# uc_board.net
KiCad netlist of a schematic drawn in EAGLE
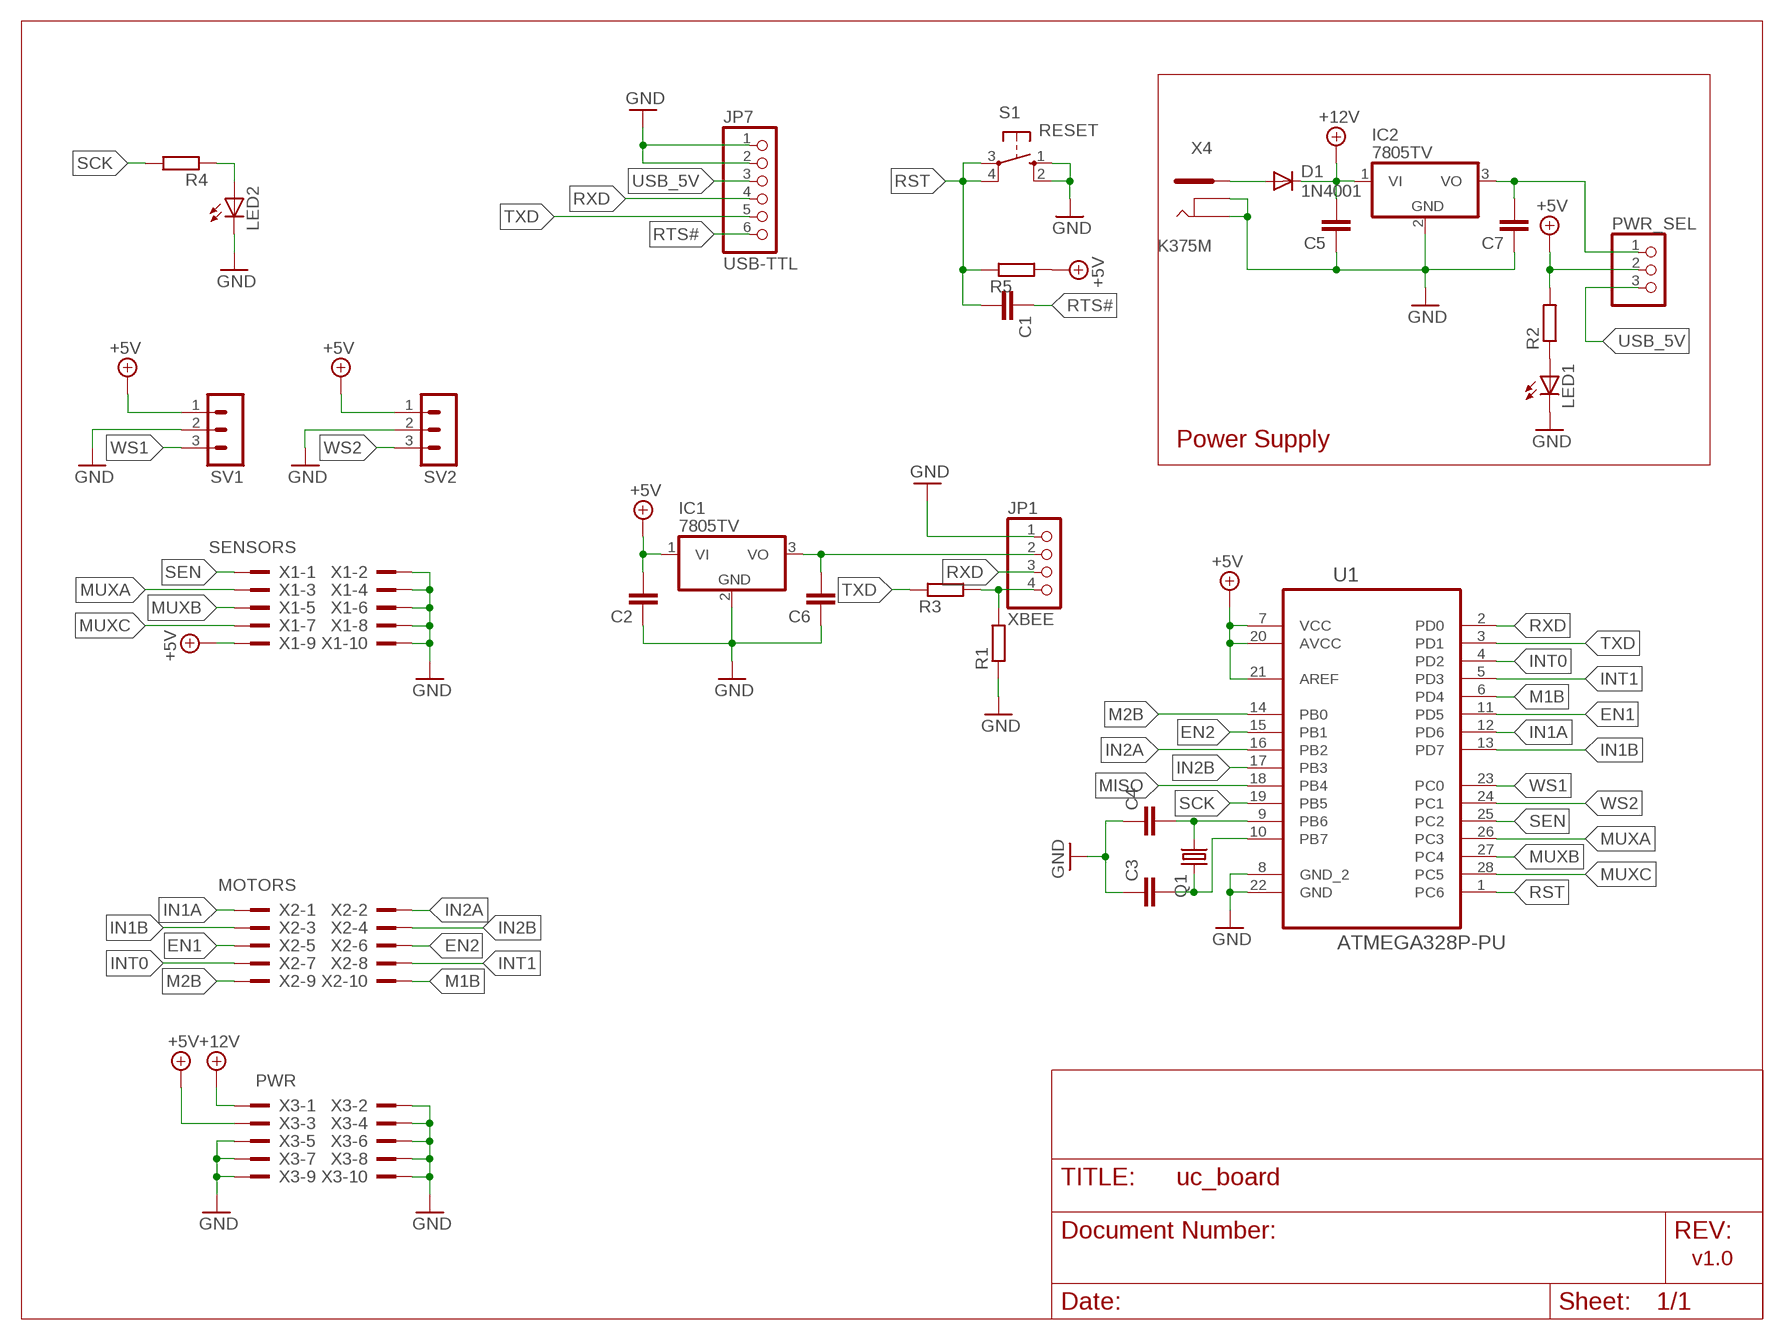
[diagram p0: schematic, sheet 1]

(export (version "E")
  (design (tool "Eeschema 10.0.6"))
  (components
    (comp (ref "C1")
      (value "C-EU050-025X075")
      (footprint "eagle-import:C050-025X075")
      (libsource (lib "eagle-import") (part "C-EU050-025X075"))
    )
    (comp (ref "C2")
      (value "C-EU025-050X050")
      (footprint "eagle-import:C025-050X050")
      (libsource (lib "eagle-import") (part "C-EU025-050X050"))
    )
    (comp (ref "C3")
      (value "C-EU050-024X044")
      (footprint "eagle-import:C050-024X044")
      (libsource (lib "eagle-import") (part "C-EU050-024X044"))
    )
    (comp (ref "C4")
      (value "C-EU050-024X044")
      (footprint "eagle-import:C050-024X044")
      (libsource (lib "eagle-import") (part "C-EU050-024X044"))
    )
    (comp (ref "C5")
      (value "C-EU025-050X050")
      (footprint "eagle-import:C025-050X050")
      (libsource (lib "eagle-import") (part "C-EU025-050X050"))
    )
    (comp (ref "C6")
      (value "C-EU025-050X050")
      (footprint "eagle-import:C025-050X050")
      (libsource (lib "eagle-import") (part "C-EU025-050X050"))
    )
    (comp (ref "C7")
      (value "C-EU025-050X050")
      (footprint "eagle-import:C025-050X050")
      (libsource (lib "eagle-import") (part "C-EU025-050X050"))
    )
    (comp (ref "D1")
      (value "1N4001")
      (footprint "eagle-import:DO41-10")
      (libsource (lib "eagle-import") (part "1N4004"))
    )
    (comp (ref "IC1")
      (value "7805TV")
      (footprint "eagle-import:TO220V")
      (libsource (lib "eagle-import") (part "78TV05"))
    )
    (comp (ref "IC2")
      (value "7805TV")
      (footprint "eagle-import:TO220V")
      (libsource (lib "eagle-import") (part "78TV05"))
    )
    (comp (ref "JP1")
      (value "XBEE")
      (footprint "eagle-import:1X04_90")
      (libsource (lib "eagle-import") (part "PINHD-1X4/90"))
    )
    (comp (ref "JP7")
      (value "USB-TTL")
      (footprint "eagle-import:1X06_90")
      (libsource (lib "eagle-import") (part "PINHD-1X6/90"))
    )
    (comp (ref "LED1")
      (value "LED5MM")
      (footprint "eagle-import:LED5MM")
      (libsource (lib "eagle-import") (part "LED5MM"))
    )
    (comp (ref "LED2")
      (value "LED5MM")
      (footprint "eagle-import:LED5MM")
      (libsource (lib "eagle-import") (part "LED5MM"))
    )
    (comp (ref "PWR_SEL")
      (value "PINHD-1X3")
      (footprint "eagle-import:1X03")
      (libsource (lib "eagle-import") (part "PINHD-1X3"))
    )
    (comp (ref "Q1")
      (value "CRYSTALHC49S")
      (footprint "eagle-import:HC49_S")
      (libsource (lib "eagle-import") (part "CRYSTALHC49S"))
    )
    (comp (ref "R1")
      (value "R-EU_0207/10")
      (footprint "eagle-import:0207_10")
      (libsource (lib "eagle-import") (part "R-EU_0207/10"))
    )
    (comp (ref "R2")
      (value "R-EU_0207/10")
      (footprint "eagle-import:0207_10")
      (libsource (lib "eagle-import") (part "R-EU_0207/10"))
    )
    (comp (ref "R3")
      (value "R-EU_0207/10")
      (footprint "eagle-import:0207_10")
      (libsource (lib "eagle-import") (part "R-EU_0207/10"))
    )
    (comp (ref "R4")
      (value "R-EU_0207/10")
      (footprint "eagle-import:0207_10")
      (libsource (lib "eagle-import") (part "R-EU_0207/10"))
    )
    (comp (ref "R5")
      (value "R-EU_0207/10")
      (footprint "eagle-import:0207_10")
      (libsource (lib "eagle-import") (part "R-EU_0207/10"))
    )
    (comp (ref "S1")
      (value "RESET")
      (footprint "eagle-import:B3F-10XX")
      (fields (field (name "MPN") "B3F-1000"))
      (libsource (lib "eagle-import") (part "10-XX"))
    )
    (comp (ref "SV1")
      (value "MA03-1")
      (footprint "eagle-import:MA03-1")
      (libsource (lib "eagle-import") (part "MA03-1"))
    )
    (comp (ref "SV2")
      (value "MA03-1")
      (footprint "eagle-import:MA03-1")
      (libsource (lib "eagle-import") (part "MA03-1"))
    )
    (comp (ref "U1")
      (value "ATMEGA328P-PU")
      (footprint "eagle-import:DIP254P762X457-28")
      (libsource (lib "eagle-import") (part "ATMEGA328P-PU"))
    )
    (comp (ref "X1")
      (value "SENSORS")
      (footprint "eagle-import:PAK100_2500-10")
      (fields (field (name "MF") "3M") (field (name "MPN") "2510-6002UB"))
      (libsource (lib "eagle-import") (part "2510-"))
    )
    (comp (ref "X2")
      (value "MOTORS")
      (footprint "eagle-import:PAK100_2500-10")
      (fields (field (name "MF") "3M") (field (name "MPN") "2510-6002UB"))
      (libsource (lib "eagle-import") (part "2510-"))
    )
    (comp (ref "X3")
      (value "PWR")
      (footprint "eagle-import:PAK100_2500-10")
      (fields (field (name "MF") "3M") (field (name "MPN") "2510-6002UB"))
      (libsource (lib "eagle-import") (part "2510-"))
    )
    (comp (ref "X4")
      (value "K375M")
      (footprint "eagle-import:K375M")
      (libsource (lib "eagle-import") (part "K375M"))
    )
  )
  (nets
    (net (code "1") (name "+5V") (class "Default")
      (node (ref "C2") (pin "2") (pinfunction "2_2") (pintype "passive"))
      (node (ref "IC1") (pin "1") (pinfunction "VI_1") (pintype "input"))
      (node (ref "PWR_SEL") (pin "2") (pinfunction "2_2") (pintype "passive"))
      (node (ref "R2") (pin "2") (pinfunction "2_2") (pintype "passive"))
      (node (ref "R5") (pin "2") (pinfunction "2_2") (pintype "passive"))
      (node (ref "SV1") (pin "1") (pinfunction "1_1") (pintype "passive"))
      (node (ref "SV2") (pin "1") (pinfunction "1_1") (pintype "passive"))
      (node (ref "U1") (pin "20") (pinfunction "AVCC_20") (pintype "power_in"))
      (node (ref "U1") (pin "21") (pinfunction "AREF_21") (pintype "input"))
      (node (ref "U1") (pin "7") (pinfunction "VCC_7") (pintype "power_in"))
      (node (ref "X1") (pin "9") (pinfunction "KL_9") (pintype "passive"))
      (node (ref "X3") (pin "3") (pinfunction "KL_3") (pintype "passive"))
    )
    (net (code "2") (name "+12V") (class "Default")
      (node (ref "C5") (pin "2") (pinfunction "2_2") (pintype "passive"))
      (node (ref "D1") (pin "C") (pinfunction "C_C") (pintype "passive"))
      (node (ref "IC2") (pin "1") (pinfunction "VI_1") (pintype "input"))
      (node (ref "X3") (pin "1") (pinfunction "KL_1") (pintype "passive"))
    )
    (net (code "3") (name "EN1") (class "Default")
      (node (ref "U1") (pin "11") (pinfunction "PD5_11") (pintype "bidirectional"))
      (node (ref "X2") (pin "5") (pinfunction "KL_5") (pintype "passive"))
    )
    (net (code "4") (name "EN2") (class "Default")
      (node (ref "U1") (pin "15") (pinfunction "PB1_15") (pintype "bidirectional"))
      (node (ref "X2") (pin "6") (pinfunction "KL_6") (pintype "passive"))
    )
    (net (code "5") (name "GND") (class "Default")
      (node (ref "C2") (pin "1") (pinfunction "1_1") (pintype "passive"))
      (node (ref "C3") (pin "1") (pinfunction "1_1") (pintype "passive"))
      (node (ref "C4") (pin "1") (pinfunction "1_1") (pintype "passive"))
      (node (ref "C5") (pin "1") (pinfunction "1_1") (pintype "passive"))
      (node (ref "C6") (pin "1") (pinfunction "1_1") (pintype "passive"))
      (node (ref "C7") (pin "1") (pinfunction "1_1") (pintype "passive"))
      (node (ref "IC1") (pin "2") (pinfunction "GND_2") (pintype "passive"))
      (node (ref "IC2") (pin "2") (pinfunction "GND_2") (pintype "passive"))
      (node (ref "JP1") (pin "1") (pinfunction "1_1") (pintype "passive"))
      (node (ref "JP7") (pin "1") (pinfunction "1_1") (pintype "passive"))
      (node (ref "JP7") (pin "2") (pinfunction "2_2") (pintype "passive"))
      (node (ref "LED1") (pin "K") (pinfunction "C_K") (pintype "passive"))
      (node (ref "LED2") (pin "K") (pinfunction "C_K") (pintype "passive"))
      (node (ref "R1") (pin "1") (pinfunction "1_1") (pintype "passive"))
      (node (ref "S1") (pin "1") (pinfunction "S_1") (pintype "passive"))
      (node (ref "S1") (pin "2") (pinfunction "S1_2") (pintype "passive"))
      (node (ref "SV1") (pin "2") (pinfunction "2_2") (pintype "passive"))
      (node (ref "SV2") (pin "2") (pinfunction "2_2") (pintype "passive"))
      (node (ref "U1") (pin "22") (pinfunction "GND_22") (pintype "passive"))
      (node (ref "U1") (pin "8") (pinfunction "GND_2_8") (pintype "passive"))
      (node (ref "X1") (pin "10") (pinfunction "KL_10") (pintype "passive"))
      (node (ref "X1") (pin "2") (pinfunction "KL_2") (pintype "passive"))
      (node (ref "X1") (pin "4") (pinfunction "KL_4") (pintype "passive"))
      (node (ref "X1") (pin "6") (pinfunction "KL_6") (pintype "passive"))
      (node (ref "X1") (pin "8") (pinfunction "KL_8") (pintype "passive"))
      (node (ref "X3") (pin "10") (pinfunction "KL_10") (pintype "passive"))
      (node (ref "X3") (pin "2") (pinfunction "KL_2") (pintype "passive"))
      (node (ref "X3") (pin "4") (pinfunction "KL_4") (pintype "passive"))
      (node (ref "X3") (pin "5") (pinfunction "KL_5") (pintype "passive"))
      (node (ref "X3") (pin "6") (pinfunction "KL_6") (pintype "passive"))
      (node (ref "X3") (pin "7") (pinfunction "KL_7") (pintype "passive"))
      (node (ref "X3") (pin "8") (pinfunction "KL_8") (pintype "passive"))
      (node (ref "X3") (pin "9") (pinfunction "KL_9") (pintype "passive"))
      (node (ref "X4") (pin "2") (pinfunction "2_2") (pintype "passive"))
      (node (ref "X4") (pin "3") (pinfunction "3_3") (pintype "passive"))
    )
    (net (code "6") (name "IN1A") (class "Default")
      (node (ref "U1") (pin "12") (pinfunction "PD6_12") (pintype "bidirectional"))
      (node (ref "X2") (pin "1") (pinfunction "KL_1") (pintype "passive"))
    )
    (net (code "7") (name "IN1B") (class "Default")
      (node (ref "U1") (pin "13") (pinfunction "PD7_13") (pintype "bidirectional"))
      (node (ref "X2") (pin "3") (pinfunction "KL_3") (pintype "passive"))
    )
    (net (code "8") (name "IN2A") (class "Default")
      (node (ref "U1") (pin "16") (pinfunction "PB2_16") (pintype "bidirectional"))
      (node (ref "X2") (pin "2") (pinfunction "KL_2") (pintype "passive"))
    )
    (net (code "9") (name "IN2B") (class "Default")
      (node (ref "U1") (pin "17") (pinfunction "PB3_17") (pintype "bidirectional"))
      (node (ref "X2") (pin "4") (pinfunction "KL_4") (pintype "passive"))
    )
    (net (code "10") (name "INT0") (class "Default")
      (node (ref "U1") (pin "4") (pinfunction "PD2_4") (pintype "bidirectional"))
      (node (ref "X2") (pin "7") (pinfunction "KL_7") (pintype "passive"))
    )
    (net (code "11") (name "INT1") (class "Default")
      (node (ref "U1") (pin "5") (pinfunction "PD3_5") (pintype "bidirectional"))
      (node (ref "X2") (pin "8") (pinfunction "KL_8") (pintype "passive"))
    )
    (net (code "12") (name "M1B") (class "Default")
      (node (ref "U1") (pin "6") (pinfunction "PD4_6") (pintype "bidirectional"))
      (node (ref "X2") (pin "10") (pinfunction "KL_10") (pintype "passive"))
    )
    (net (code "13") (name "M2B") (class "Default")
      (node (ref "U1") (pin "14") (pinfunction "PB0_14") (pintype "bidirectional"))
      (node (ref "X2") (pin "9") (pinfunction "KL_9") (pintype "passive"))
    )
    (net (code "14") (name "MISO") (class "Default")
      (node (ref "U1") (pin "18") (pinfunction "PB4_18") (pintype "bidirectional"))
    )
    (net (code "15") (name "MUXA") (class "Default")
      (node (ref "U1") (pin "26") (pinfunction "PC3_26") (pintype "bidirectional"))
      (node (ref "X1") (pin "3") (pinfunction "KL_3") (pintype "passive"))
    )
    (net (code "16") (name "MUXB") (class "Default")
      (node (ref "U1") (pin "27") (pinfunction "PC4_27") (pintype "bidirectional"))
      (node (ref "X1") (pin "5") (pinfunction "KL_5") (pintype "passive"))
    )
    (net (code "17") (name "MUXC") (class "Default")
      (node (ref "U1") (pin "28") (pinfunction "PC5_28") (pintype "bidirectional"))
      (node (ref "X1") (pin "7") (pinfunction "KL_7") (pintype "passive"))
    )
    (net (code "18") (name "Net-(D1-PadA)") (class "Default")
      (node (ref "D1") (pin "A") (pinfunction "A_A") (pintype "passive"))
      (node (ref "X4") (pin "1") (pinfunction "1_1") (pintype "passive"))
    )
    (net (code "19") (name "Net-(IC1-VO)") (class "Default")
      (node (ref "C6") (pin "2") (pinfunction "2_2") (pintype "passive"))
      (node (ref "IC1") (pin "3") (pinfunction "VO_3") (pintype "passive"))
      (node (ref "JP1") (pin "2") (pinfunction "2_2") (pintype "passive"))
    )
    (net (code "20") (name "Net-(IC2-VO)") (class "Default")
      (node (ref "C7") (pin "2") (pinfunction "2_2") (pintype "passive"))
      (node (ref "IC2") (pin "3") (pinfunction "VO_3") (pintype "passive"))
      (node (ref "PWR_SEL") (pin "1") (pinfunction "1_1") (pintype "passive"))
    )
    (net (code "21") (name "Net-(JP1-Pad4)") (class "Default")
      (node (ref "JP1") (pin "4") (pinfunction "4_4") (pintype "passive"))
      (node (ref "R1") (pin "2") (pinfunction "2_2") (pintype "passive"))
      (node (ref "R3") (pin "2") (pinfunction "2_2") (pintype "passive"))
    )
    (net (code "22") (name "Net-(LED1-PadA)") (class "Default")
      (node (ref "LED1") (pin "A") (pinfunction "A_A") (pintype "passive"))
      (node (ref "R2") (pin "1") (pinfunction "1_1") (pintype "passive"))
    )
    (net (code "23") (name "Net-(LED2-PadA)") (class "Default")
      (node (ref "LED2") (pin "A") (pinfunction "A_A") (pintype "passive"))
      (node (ref "R4") (pin "1") (pinfunction "1_1") (pintype "passive"))
    )
    (net (code "24") (name "Net-(U1-PB6)") (class "Default")
      (node (ref "C4") (pin "2") (pinfunction "2_2") (pintype "passive"))
      (node (ref "Q1") (pin "1") (pinfunction "1_1") (pintype "passive"))
      (node (ref "U1") (pin "9") (pinfunction "PB6_9") (pintype "bidirectional"))
    )
    (net (code "25") (name "Net-(U1-PB7)") (class "Default")
      (node (ref "C3") (pin "2") (pinfunction "2_2") (pintype "passive"))
      (node (ref "Q1") (pin "2") (pinfunction "2_2") (pintype "passive"))
      (node (ref "U1") (pin "10") (pinfunction "PB7_10") (pintype "bidirectional"))
    )
    (net (code "26") (name "RST") (class "Default")
      (node (ref "C1") (pin "2") (pinfunction "2_2") (pintype "passive"))
      (node (ref "R5") (pin "1") (pinfunction "1_1") (pintype "passive"))
      (node (ref "S1") (pin "3") (pinfunction "P_3") (pintype "passive"))
      (node (ref "S1") (pin "4") (pinfunction "P1_4") (pintype "passive"))
      (node (ref "U1") (pin "1") (pinfunction "PC6_1") (pintype "bidirectional"))
    )
    (net (code "27") (name "RTS#") (class "Default")
      (node (ref "C1") (pin "1") (pinfunction "1_1") (pintype "passive"))
      (node (ref "JP7") (pin "6") (pinfunction "6_6") (pintype "passive"))
    )
    (net (code "28") (name "RXD") (class "Default")
      (node (ref "JP1") (pin "3") (pinfunction "3_3") (pintype "passive"))
      (node (ref "JP7") (pin "4") (pinfunction "4_4") (pintype "passive"))
      (node (ref "U1") (pin "2") (pinfunction "PD0_2") (pintype "bidirectional"))
    )
    (net (code "29") (name "SCK") (class "Default")
      (node (ref "R4") (pin "2") (pinfunction "2_2") (pintype "passive"))
      (node (ref "U1") (pin "19") (pinfunction "PB5_19") (pintype "bidirectional"))
    )
    (net (code "30") (name "SEN") (class "Default")
      (node (ref "U1") (pin "25") (pinfunction "PC2_25") (pintype "bidirectional"))
      (node (ref "X1") (pin "1") (pinfunction "KL_1") (pintype "passive"))
    )
    (net (code "31") (name "TXD") (class "Default")
      (node (ref "JP7") (pin "5") (pinfunction "5_5") (pintype "passive"))
      (node (ref "R3") (pin "1") (pinfunction "1_1") (pintype "passive"))
      (node (ref "U1") (pin "3") (pinfunction "PD1_3") (pintype "bidirectional"))
    )
    (net (code "32") (name "USB_5V") (class "Default")
      (node (ref "JP7") (pin "3") (pinfunction "3_3") (pintype "passive"))
      (node (ref "PWR_SEL") (pin "3") (pinfunction "3_3") (pintype "passive"))
    )
    (net (code "33") (name "WS1") (class "Default")
      (node (ref "SV1") (pin "3") (pinfunction "3_3") (pintype "passive"))
      (node (ref "U1") (pin "23") (pinfunction "PC0_23") (pintype "bidirectional"))
    )
    (net (code "34") (name "WS2") (class "Default")
      (node (ref "SV2") (pin "3") (pinfunction "3_3") (pintype "passive"))
      (node (ref "U1") (pin "24") (pinfunction "PC1_24") (pintype "bidirectional"))
    )
  )
)
